# SensorBoard.net
KiCad netlist of a schematic drawn in EAGLE
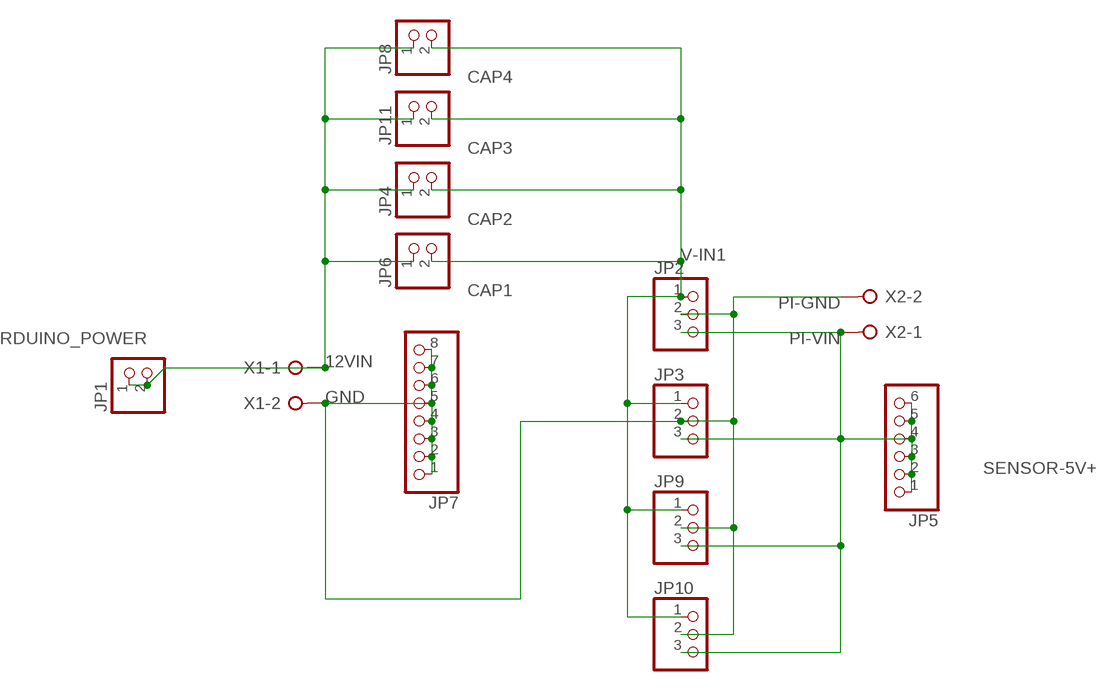
[diagram p0: schematic, sheet 1]

(export (version "E")
  (design (tool "Eeschema 10.0.6"))
  (components
    (comp (ref "JP1")
      (value "PINHD-1X2")
      (footprint "eagle-import:1X02")
      (libsource (lib "eagle-import") (part "PINHD-1X2"))
    )
    (comp (ref "JP2")
      (value "PINHD-1X3")
      (footprint "eagle-import:1X03")
      (libsource (lib "eagle-import") (part "PINHD-1X3"))
    )
    (comp (ref "JP3")
      (value "PINHD-1X3")
      (footprint "eagle-import:1X03")
      (libsource (lib "eagle-import") (part "PINHD-1X3"))
    )
    (comp (ref "JP4")
      (value "PINHD-1X2")
      (footprint "eagle-import:1X02")
      (libsource (lib "eagle-import") (part "PINHD-1X2"))
    )
    (comp (ref "JP5")
      (value "PINHD-1X6")
      (footprint "eagle-import:1X06")
      (libsource (lib "eagle-import") (part "PINHD-1X6"))
    )
    (comp (ref "JP6")
      (value "PINHD-1X2")
      (footprint "eagle-import:1X02")
      (libsource (lib "eagle-import") (part "PINHD-1X2"))
    )
    (comp (ref "JP7")
      (value "PINHD-1X8")
      (footprint "eagle-import:1X08")
      (libsource (lib "eagle-import") (part "PINHD-1X8"))
    )
    (comp (ref "JP8")
      (value "PINHD-1X2")
      (footprint "eagle-import:1X02")
      (libsource (lib "eagle-import") (part "PINHD-1X2"))
    )
    (comp (ref "JP9")
      (value "PINHD-1X3")
      (footprint "eagle-import:1X03")
      (libsource (lib "eagle-import") (part "PINHD-1X3"))
    )
    (comp (ref "JP10")
      (value "PINHD-1X3")
      (footprint "eagle-import:1X03")
      (libsource (lib "eagle-import") (part "PINHD-1X3"))
    )
    (comp (ref "JP11")
      (value "PINHD-1X2")
      (footprint "eagle-import:1X02")
      (libsource (lib "eagle-import") (part "PINHD-1X2"))
    )
    (comp (ref "X1")
      (value "W237-02P")
      (footprint "eagle-import:W237-132")
      (libsource (lib "eagle-import") (part "W237-02P"))
    )
    (comp (ref "X2")
      (value "W237-02P")
      (footprint "eagle-import:W237-132")
      (libsource (lib "eagle-import") (part "W237-02P"))
    )
  )
  (nets
    (net (code "1") (name "/SENSOR-5V+") (class "Default")
      (node (ref "JP10") (pin "3") (pinfunction "3_3") (pintype "passive"))
      (node (ref "JP2") (pin "3") (pinfunction "3_3") (pintype "passive"))
      (node (ref "JP3") (pin "3") (pinfunction "3_3") (pintype "passive"))
      (node (ref "JP5") (pin "1") (pinfunction "1_1") (pintype "passive"))
      (node (ref "JP5") (pin "2") (pinfunction "2_2") (pintype "passive"))
      (node (ref "JP5") (pin "3") (pinfunction "3_3") (pintype "passive"))
      (node (ref "JP5") (pin "4") (pinfunction "4_4") (pintype "passive"))
      (node (ref "JP5") (pin "5") (pinfunction "5_5") (pintype "passive"))
      (node (ref "JP5") (pin "6") (pinfunction "6_6") (pintype "passive"))
      (node (ref "JP9") (pin "3") (pinfunction "3_3") (pintype "passive"))
      (node (ref "X2") (pin "1") (pinfunction "KL_1") (pintype "passive"))
    )
    (net (code "2") (name "/V-IN1") (class "Default")
      (node (ref "JP10") (pin "1") (pinfunction "1_1") (pintype "passive"))
      (node (ref "JP11") (pin "2") (pinfunction "2_2") (pintype "passive"))
      (node (ref "JP2") (pin "1") (pinfunction "1_1") (pintype "passive"))
      (node (ref "JP3") (pin "1") (pinfunction "1_1") (pintype "passive"))
      (node (ref "JP4") (pin "2") (pinfunction "2_2") (pintype "passive"))
      (node (ref "JP6") (pin "2") (pinfunction "2_2") (pintype "passive"))
      (node (ref "JP8") (pin "2") (pinfunction "2_2") (pintype "passive"))
      (node (ref "JP9") (pin "1") (pinfunction "1_1") (pintype "passive"))
    )
    (net (code "3") (name "Net-(X1A-KL)") (class "Default")
      (node (ref "JP1") (pin "1") (pinfunction "1_1") (pintype "passive"))
      (node (ref "JP1") (pin "2") (pinfunction "2_2") (pintype "passive"))
      (node (ref "JP11") (pin "1") (pinfunction "1_1") (pintype "passive"))
      (node (ref "JP4") (pin "1") (pinfunction "1_1") (pintype "passive"))
      (node (ref "JP6") (pin "1") (pinfunction "1_1") (pintype "passive"))
      (node (ref "JP8") (pin "1") (pinfunction "1_1") (pintype "passive"))
      (node (ref "X1") (pin "1") (pinfunction "KL_1") (pintype "passive"))
    )
    (net (code "4") (name "Net-(X1B-KL)") (class "Default")
      (node (ref "JP10") (pin "2") (pinfunction "2_2") (pintype "passive"))
      (node (ref "JP2") (pin "2") (pinfunction "2_2") (pintype "passive"))
      (node (ref "JP3") (pin "2") (pinfunction "2_2") (pintype "passive"))
      (node (ref "JP7") (pin "1") (pinfunction "1_1") (pintype "passive"))
      (node (ref "JP7") (pin "2") (pinfunction "2_2") (pintype "passive"))
      (node (ref "JP7") (pin "3") (pinfunction "3_3") (pintype "passive"))
      (node (ref "JP7") (pin "4") (pinfunction "4_4") (pintype "passive"))
      (node (ref "JP7") (pin "5") (pinfunction "5_5") (pintype "passive"))
      (node (ref "JP7") (pin "6") (pinfunction "6_6") (pintype "passive"))
      (node (ref "JP7") (pin "7") (pinfunction "7_7") (pintype "passive"))
      (node (ref "JP7") (pin "8") (pinfunction "8_8") (pintype "passive"))
      (node (ref "JP9") (pin "2") (pinfunction "2_2") (pintype "passive"))
      (node (ref "X1") (pin "2") (pinfunction "KL_2") (pintype "passive"))
      (node (ref "X2") (pin "2") (pinfunction "KL_2") (pintype "passive"))
    )
  )
)
